# Reefing-IMU.net
KiCad netlist of a schematic drawn in Altium Designer
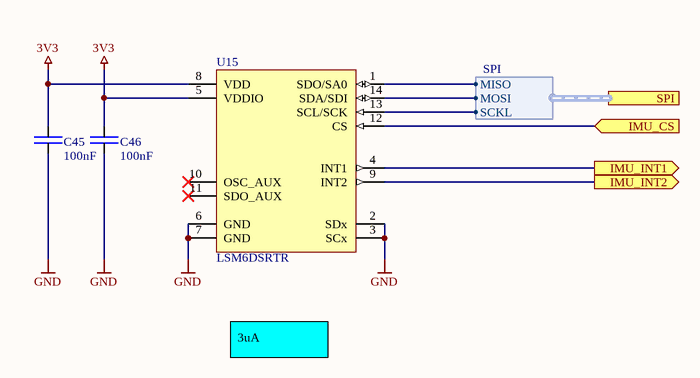
[diagram p0: Reefing-IMU.SchDoc]

(export (version "E")
  (design (tool "Eeschema 10.0.6"))
  (components
    (comp (ref "C45")
      (value "100nF")
      (footprint "SMD Keramikkondensator 0402")
      (description "SMD Ceramic Capacitor E6")
      (libsource (lib "CATS-EUROC") (part "E6 - 100nF"))
    )
    (comp (ref "C46")
      (value "100nF")
      (footprint "SMD Keramikkondensator 0402")
      (description "SMD Ceramic Capacitor E6")
      (libsource (lib "CATS-EUROC") (part "E6 - 100nF"))
    )
    (comp (ref "U15")
      (value "LSM6DSRTR")
      (footprint "SMD IC LGA-14")
      (description "Accelerometer, Gyroscope, Temperature, 6 Axis Sensor I²C, SPI Output")
      (libsource (lib "Sensors") (part "LSM6DSRTR"))
    )
  )
  (nets
    (net (code "2") (name "/IMU_CS") (class "Default")
      (node (ref "U15") (pin "12") (pinfunction "CS_12") (pintype "input"))
    )
    (net (code "3") (name "/IMU_INT1") (class "Default")
      (node (ref "U15") (pin "4") (pinfunction "INT1_4") (pintype "output"))
    )
    (net (code "4") (name "/IMU_INT2") (class "Default")
      (node (ref "U15") (pin "9") (pinfunction "INT2_9") (pintype "output"))
    )
    (net (code "5") (name "/MISO") (class "Default")
      (node (ref "U15") (pin "1") (pinfunction "SDO/SA0_1") (pintype "bidirectional"))
    )
    (net (code "6") (name "/MOSI") (class "Default")
      (node (ref "U15") (pin "14") (pinfunction "SDA/SDI_14") (pintype "bidirectional"))
    )
    (net (code "7") (name "/SCKL") (class "Default")
      (node (ref "U15") (pin "13") (pinfunction "SCL/SCK_13") (pintype "input"))
    )
    (net (code "9") (name "3V3") (class "Default")
      (node (ref "C45") (pin "2") (pinfunction "2_2") (pintype "passive"))
      (node (ref "C46") (pin "2") (pinfunction "2_2") (pintype "passive"))
      (node (ref "U15") (pin "5") (pinfunction "VDDIO_5") (pintype "passive"))
      (node (ref "U15") (pin "8") (pinfunction "VDD_8") (pintype "passive"))
    )
    (net (code "10") (name "GND") (class "Default")
      (node (ref "C45") (pin "1") (pinfunction "1_1") (pintype "passive"))
      (node (ref "C46") (pin "1") (pinfunction "1_1") (pintype "passive"))
      (node (ref "U15") (pin "2") (pinfunction "SDx_2") (pintype "passive"))
      (node (ref "U15") (pin "3") (pinfunction "SCx_3") (pintype "passive"))
      (node (ref "U15") (pin "6") (pinfunction "GND_6") (pintype "passive"))
      (node (ref "U15") (pin "7") (pinfunction "GND_7") (pintype "passive"))
    )
    (net (code "11") (name "unconnected-(U15-OSC_AUX-Pad10)") (class "Default")
      (node (ref "U15") (pin "10") (pinfunction "OSC_AUX_10") (pintype "passive+no_connect"))
    )
    (net (code "12") (name "unconnected-(U15-SDO_AUX-Pad11)") (class "Default")
      (node (ref "U15") (pin "11") (pinfunction "SDO_AUX_11") (pintype "passive+no_connect"))
    )
  )
)
